# 11_FlashMemory.net
KiCad netlist of a schematic drawn in Altium Designer
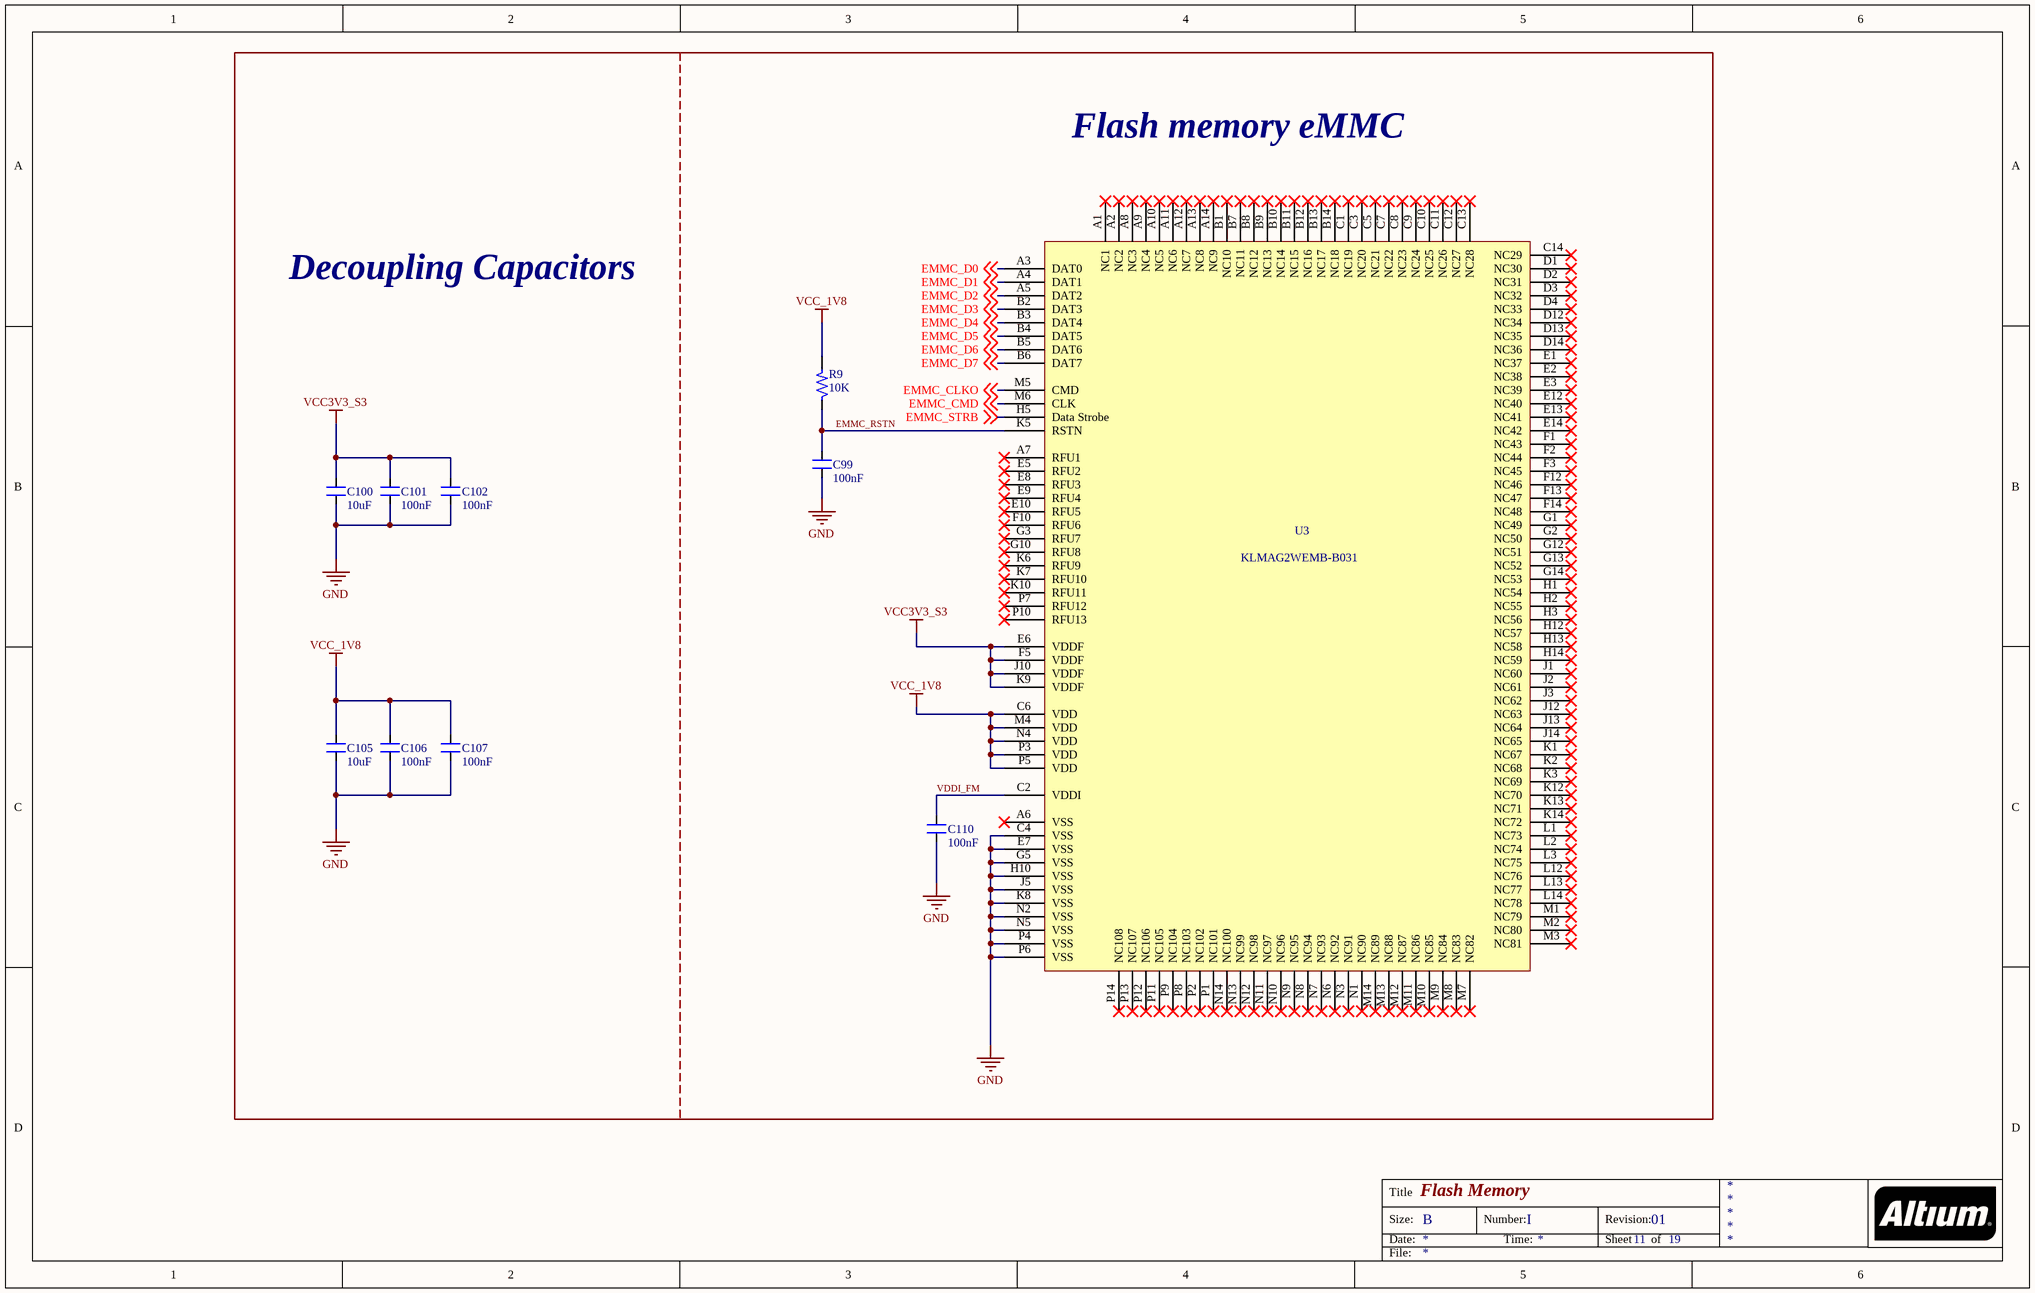
[diagram p0: [11] FlashMemory.SchDoc]

(export (version "E")
  (design (tool "Eeschema 10.0.6"))
  (components
    (comp (ref "C99")
      (value "100nF")
      (footprint "CAP_0201")
      (description "0.1µF ±10% 25V Ceramic Capacitor X5R 0201 (0603 Metric)")
      (fields
        (field (name "MANUFACTURER") "TDK Corporation")
        (field (name "MANUFACTURER PART NUMBER") "C0603X5R1E104K030BB")
      )
      (libsource (lib "EsteemPCB_SOM_Course_intlib") (part "CAP_100nF-25V-10%-0201"))
    )
    (comp (ref "C100")
      (value "10uF")
      (footprint "CAP_0603")
      (description "10µF ±10% 25V Ceramic Capacitor X5R 0603 (1608 Metric)")
      (fields
        (field (name "MANUFACTURER") "Murata Electronics")
        (field (name "MANUFACTURER PART NUMBER") "GRM188R61E106KA73D")
      )
      (libsource (lib "EsteemPCB_SOM_Course_intlib") (part "CAP_10uF-25V-10%-0603"))
    )
    (comp (ref "C101")
      (value "100nF")
      (footprint "CAP_0201")
      (description "0.1µF ±10% 25V Ceramic Capacitor X5R 0201 (0603 Metric)")
      (fields
        (field (name "MANUFACTURER") "TDK Corporation")
        (field (name "MANUFACTURER PART NUMBER") "C0603X5R1E104K030BB")
      )
      (libsource (lib "EsteemPCB_SOM_Course_intlib") (part "CAP_100nF-25V-10%-0201"))
    )
    (comp (ref "C102")
      (value "100nF")
      (footprint "CAP_0201")
      (description "0.1µF ±10% 25V Ceramic Capacitor X5R 0201 (0603 Metric)")
      (fields
        (field (name "MANUFACTURER") "TDK Corporation")
        (field (name "MANUFACTURER PART NUMBER") "C0603X5R1E104K030BB")
      )
      (libsource (lib "EsteemPCB_SOM_Course_intlib") (part "CAP_100nF-25V-10%-0201"))
    )
    (comp (ref "C105")
      (value "10uF")
      (footprint "CAP_0603")
      (description "10µF ±10% 25V Ceramic Capacitor X5R 0603 (1608 Metric)")
      (fields
        (field (name "MANUFACTURER") "Murata Electronics")
        (field (name "MANUFACTURER PART NUMBER") "GRM188R61E106KA73D")
      )
      (libsource (lib "EsteemPCB_SOM_Course_intlib") (part "CAP_10uF-25V-10%-0603"))
    )
    (comp (ref "C106")
      (value "100nF")
      (footprint "CAP_0201")
      (description "0.1µF ±10% 25V Ceramic Capacitor X5R 0201 (0603 Metric)")
      (fields
        (field (name "MANUFACTURER") "TDK Corporation")
        (field (name "MANUFACTURER PART NUMBER") "C0603X5R1E104K030BB")
      )
      (libsource (lib "EsteemPCB_SOM_Course_intlib") (part "CAP_100nF-25V-10%-0201"))
    )
    (comp (ref "C107")
      (value "100nF")
      (footprint "CAP_0201")
      (description "0.1µF ±10% 25V Ceramic Capacitor X5R 0201 (0603 Metric)")
      (fields
        (field (name "MANUFACTURER") "TDK Corporation")
        (field (name "MANUFACTURER PART NUMBER") "C0603X5R1E104K030BB")
      )
      (libsource (lib "EsteemPCB_SOM_Course_intlib") (part "CAP_100nF-25V-10%-0201"))
    )
    (comp (ref "C110")
      (value "100nF")
      (footprint "CAP_0201")
      (description "0.1µF ±10% 25V Ceramic Capacitor X5R 0201 (0603 Metric)")
      (fields
        (field (name "MANUFACTURER") "TDK Corporation")
        (field (name "MANUFACTURER PART NUMBER") "C0603X5R1E104K030BB")
      )
      (libsource (lib "EsteemPCB_SOM_Course_intlib") (part "CAP_100nF-25V-10%-0201"))
    )
    (comp (ref "R9")
      (value "10K")
      (footprint "RES_0201")
      (description "10 kOhms ±1% 0.05W, 1/20W Chip Resistor 0201 (0603 Metric) Thick Film")
      (fields
        (field (name "MANUFACTURER") "Stackpole Electronics Inc")
        (field (name "MANUFACTURER PART NUMBER") "RMCF0201FT10K0")
      )
      (libsource (lib "EsteemPCB_SOM_Course_intlib") (part "RES_10K-0.05W-1%-0201"))
    )
    (comp (ref "U3")
      (value "KLMAG2WEMB-B031")
      (footprint "BGA153C50P14X14_1150X1300X70")
      (description "16GB NAND Flash Memory")
      (fields (field (name "MANUFACTURER") "Samsung Electronics"))
      (libsource (lib "EsteemPCB_SOM_Course_intlib") (part "IC_KLMAG2WEMB-B031"))
    )
  )
  (nets
    (net (code "1") (name "/EMMC_RSTN") (class "Default")
      (node (ref "C99") (pin "2") (pinfunction "2_2") (pintype "passive"))
      (node (ref "R9") (pin "1") (pinfunction "1_1") (pintype "passive"))
      (node (ref "U3") (pin "K5") (pinfunction "RSTN_K5") (pintype "passive"))
    )
    (net (code "2") (name "/VDDI_FM") (class "Default")
      (node (ref "C110") (pin "2") (pinfunction "2_2") (pintype "passive"))
      (node (ref "U3") (pin "C2") (pinfunction "VDDI_C2") (pintype "passive"))
    )
    (net (code "3") (name "EMMC_CLKO") (class "Default")
      (node (ref "U3") (pin "M5") (pinfunction "CMD_M5") (pintype "passive"))
    )
    (net (code "4") (name "EMMC_CMD") (class "Default")
      (node (ref "U3") (pin "M6") (pinfunction "CLK_M6") (pintype "passive"))
    )
    (net (code "5") (name "EMMC_D0") (class "Default")
      (node (ref "U3") (pin "A3") (pinfunction "DAT0_A3") (pintype "passive"))
    )
    (net (code "6") (name "EMMC_D1") (class "Default")
      (node (ref "U3") (pin "A4") (pinfunction "DAT1_A4") (pintype "passive"))
    )
    (net (code "7") (name "EMMC_D2") (class "Default")
      (node (ref "U3") (pin "A5") (pinfunction "DAT2_A5") (pintype "passive"))
    )
    (net (code "8") (name "EMMC_D3") (class "Default")
      (node (ref "U3") (pin "B2") (pinfunction "DAT3_B2") (pintype "passive"))
    )
    (net (code "9") (name "EMMC_D4") (class "Default")
      (node (ref "U3") (pin "B3") (pinfunction "DAT4_B3") (pintype "passive"))
    )
    (net (code "10") (name "EMMC_D5") (class "Default")
      (node (ref "U3") (pin "B4") (pinfunction "DAT5_B4") (pintype "passive"))
    )
    (net (code "11") (name "EMMC_D6") (class "Default")
      (node (ref "U3") (pin "B5") (pinfunction "DAT6_B5") (pintype "passive"))
    )
    (net (code "12") (name "EMMC_D7") (class "Default")
      (node (ref "U3") (pin "B6") (pinfunction "DAT7_B6") (pintype "passive"))
    )
    (net (code "13") (name "EMMC_STRB") (class "Default")
      (node (ref "U3") (pin "H5") (pinfunction "Data_Strobe_H5") (pintype "passive"))
    )
    (net (code "14") (name "GND") (class "Default")
      (node (ref "C100") (pin "1") (pinfunction "1_1") (pintype "passive"))
      (node (ref "C101") (pin "1") (pinfunction "1_1") (pintype "passive"))
      (node (ref "C102") (pin "1") (pinfunction "1_1") (pintype "passive"))
      (node (ref "C105") (pin "1") (pinfunction "1_1") (pintype "passive"))
      (node (ref "C106") (pin "1") (pinfunction "1_1") (pintype "passive"))
      (node (ref "C107") (pin "1") (pinfunction "1_1") (pintype "passive"))
      (node (ref "C110") (pin "1") (pinfunction "1_1") (pintype "passive"))
      (node (ref "C99") (pin "1") (pinfunction "1_1") (pintype "passive"))
      (node (ref "U3") (pin "C4") (pinfunction "VSS_C4") (pintype "passive"))
      (node (ref "U3") (pin "E7") (pinfunction "VSS_E7") (pintype "passive"))
      (node (ref "U3") (pin "G5") (pinfunction "VSS_G5") (pintype "passive"))
      (node (ref "U3") (pin "H10") (pinfunction "VSS_H10") (pintype "passive"))
      (node (ref "U3") (pin "J5") (pinfunction "VSS_J5") (pintype "passive"))
      (node (ref "U3") (pin "K8") (pinfunction "VSS_K8") (pintype "passive"))
      (node (ref "U3") (pin "N2") (pinfunction "VSS_N2") (pintype "passive"))
      (node (ref "U3") (pin "N5") (pinfunction "VSS_N5") (pintype "passive"))
      (node (ref "U3") (pin "P4") (pinfunction "VSS_P4") (pintype "passive"))
      (node (ref "U3") (pin "P6") (pinfunction "VSS_P6") (pintype "passive"))
    )
    (net (code "15") (name "VCC3V3_S3") (class "Default")
      (node (ref "C100") (pin "2") (pinfunction "2_2") (pintype "passive"))
      (node (ref "C101") (pin "2") (pinfunction "2_2") (pintype "passive"))
      (node (ref "C102") (pin "2") (pinfunction "2_2") (pintype "passive"))
      (node (ref "U3") (pin "E6") (pinfunction "VDDF_E6") (pintype "passive"))
      (node (ref "U3") (pin "F5") (pinfunction "VDDF_F5") (pintype "passive"))
      (node (ref "U3") (pin "J10") (pinfunction "VDDF_J10") (pintype "passive"))
      (node (ref "U3") (pin "K9") (pinfunction "VDDF_K9") (pintype "passive"))
    )
    (net (code "16") (name "VCC_1V8") (class "Default")
      (node (ref "C105") (pin "2") (pinfunction "2_2") (pintype "passive"))
      (node (ref "C106") (pin "2") (pinfunction "2_2") (pintype "passive"))
      (node (ref "C107") (pin "2") (pinfunction "2_2") (pintype "passive"))
      (node (ref "R9") (pin "2") (pinfunction "2_2") (pintype "passive"))
      (node (ref "U3") (pin "C6") (pinfunction "VDD_C6") (pintype "passive"))
      (node (ref "U3") (pin "M4") (pinfunction "VDD_M4") (pintype "passive"))
      (node (ref "U3") (pin "N4") (pinfunction "VDD_N4") (pintype "passive"))
      (node (ref "U3") (pin "P3") (pinfunction "VDD_P3") (pintype "passive"))
      (node (ref "U3") (pin "P5") (pinfunction "VDD_P5") (pintype "passive"))
    )
    (net (code "17") (name "unconnected-(U3-NC1-PadA1)") (class "Default")
      (node (ref "U3") (pin "A1") (pinfunction "NC1_A1") (pintype "passive+no_connect"))
    )
    (net (code "18") (name "unconnected-(U3-NC2-PadA2)") (class "Default")
      (node (ref "U3") (pin "A2") (pinfunction "NC2_A2") (pintype "passive+no_connect"))
    )
    (net (code "19") (name "unconnected-(U3-NC3-PadA8)") (class "Default")
      (node (ref "U3") (pin "A8") (pinfunction "NC3_A8") (pintype "passive+no_connect"))
    )
    (net (code "20") (name "unconnected-(U3-NC4-PadA9)") (class "Default")
      (node (ref "U3") (pin "A9") (pinfunction "NC4_A9") (pintype "passive+no_connect"))
    )
    (net (code "21") (name "unconnected-(U3-NC5-PadA10)") (class "Default")
      (node (ref "U3") (pin "A10") (pinfunction "NC5_A10") (pintype "passive+no_connect"))
    )
    (net (code "22") (name "unconnected-(U3-NC6-PadA11)") (class "Default")
      (node (ref "U3") (pin "A11") (pinfunction "NC6_A11") (pintype "passive+no_connect"))
    )
    (net (code "23") (name "unconnected-(U3-NC7-PadA12)") (class "Default")
      (node (ref "U3") (pin "A12") (pinfunction "NC7_A12") (pintype "passive+no_connect"))
    )
    (net (code "24") (name "unconnected-(U3-NC8-PadA13)") (class "Default")
      (node (ref "U3") (pin "A13") (pinfunction "NC8_A13") (pintype "passive+no_connect"))
    )
    (net (code "25") (name "unconnected-(U3-NC9-PadA14)") (class "Default")
      (node (ref "U3") (pin "A14") (pinfunction "NC9_A14") (pintype "passive+no_connect"))
    )
    (net (code "26") (name "unconnected-(U3-NC10-PadB1)") (class "Default")
      (node (ref "U3") (pin "B1") (pinfunction "NC10_B1") (pintype "passive+no_connect"))
    )
    (net (code "27") (name "unconnected-(U3-NC11-PadB7)") (class "Default")
      (node (ref "U3") (pin "B7") (pinfunction "NC11_B7") (pintype "passive+no_connect"))
    )
    (net (code "28") (name "unconnected-(U3-NC12-PadB8)") (class "Default")
      (node (ref "U3") (pin "B8") (pinfunction "NC12_B8") (pintype "passive+no_connect"))
    )
    (net (code "29") (name "unconnected-(U3-NC13-PadB9)") (class "Default")
      (node (ref "U3") (pin "B9") (pinfunction "NC13_B9") (pintype "passive+no_connect"))
    )
    (net (code "30") (name "unconnected-(U3-NC14-PadB10)") (class "Default")
      (node (ref "U3") (pin "B10") (pinfunction "NC14_B10") (pintype "passive+no_connect"))
    )
    (net (code "31") (name "unconnected-(U3-NC15-PadB11)") (class "Default")
      (node (ref "U3") (pin "B11") (pinfunction "NC15_B11") (pintype "passive+no_connect"))
    )
    (net (code "32") (name "unconnected-(U3-NC16-PadB12)") (class "Default")
      (node (ref "U3") (pin "B12") (pinfunction "NC16_B12") (pintype "passive+no_connect"))
    )
    (net (code "33") (name "unconnected-(U3-NC17-PadB13)") (class "Default")
      (node (ref "U3") (pin "B13") (pinfunction "NC17_B13") (pintype "passive+no_connect"))
    )
    (net (code "34") (name "unconnected-(U3-NC18-PadB14)") (class "Default")
      (node (ref "U3") (pin "B14") (pinfunction "NC18_B14") (pintype "passive+no_connect"))
    )
    (net (code "35") (name "unconnected-(U3-NC19-PadC1)") (class "Default")
      (node (ref "U3") (pin "C1") (pinfunction "NC19_C1") (pintype "passive+no_connect"))
    )
    (net (code "36") (name "unconnected-(U3-NC20-PadC3)") (class "Default")
      (node (ref "U3") (pin "C3") (pinfunction "NC20_C3") (pintype "passive+no_connect"))
    )
    (net (code "37") (name "unconnected-(U3-NC21-PadC5)") (class "Default")
      (node (ref "U3") (pin "C5") (pinfunction "NC21_C5") (pintype "passive+no_connect"))
    )
    (net (code "38") (name "unconnected-(U3-NC22-PadC7)") (class "Default")
      (node (ref "U3") (pin "C7") (pinfunction "NC22_C7") (pintype "passive+no_connect"))
    )
    (net (code "39") (name "unconnected-(U3-NC23-PadC8)") (class "Default")
      (node (ref "U3") (pin "C8") (pinfunction "NC23_C8") (pintype "passive+no_connect"))
    )
    (net (code "40") (name "unconnected-(U3-NC24-PadC9)") (class "Default")
      (node (ref "U3") (pin "C9") (pinfunction "NC24_C9") (pintype "passive+no_connect"))
    )
    (net (code "41") (name "unconnected-(U3-NC25-PadC10)") (class "Default")
      (node (ref "U3") (pin "C10") (pinfunction "NC25_C10") (pintype "passive+no_connect"))
    )
    (net (code "42") (name "unconnected-(U3-NC26-PadC11)") (class "Default")
      (node (ref "U3") (pin "C11") (pinfunction "NC26_C11") (pintype "passive+no_connect"))
    )
    (net (code "43") (name "unconnected-(U3-NC27-PadC12)") (class "Default")
      (node (ref "U3") (pin "C12") (pinfunction "NC27_C12") (pintype "passive+no_connect"))
    )
    (net (code "44") (name "unconnected-(U3-NC28-PadC13)") (class "Default")
      (node (ref "U3") (pin "C13") (pinfunction "NC28_C13") (pintype "passive+no_connect"))
    )
    (net (code "45") (name "unconnected-(U3-NC29-PadC14)") (class "Default")
      (node (ref "U3") (pin "C14") (pinfunction "NC29_C14") (pintype "passive+no_connect"))
    )
    (net (code "46") (name "unconnected-(U3-NC30-PadD1)") (class "Default")
      (node (ref "U3") (pin "D1") (pinfunction "NC30_D1") (pintype "passive+no_connect"))
    )
    (net (code "47") (name "unconnected-(U3-NC31-PadD2)") (class "Default")
      (node (ref "U3") (pin "D2") (pinfunction "NC31_D2") (pintype "passive+no_connect"))
    )
    (net (code "48") (name "unconnected-(U3-NC32-PadD3)") (class "Default")
      (node (ref "U3") (pin "D3") (pinfunction "NC32_D3") (pintype "passive+no_connect"))
    )
    (net (code "49") (name "unconnected-(U3-NC33-PadD4)") (class "Default")
      (node (ref "U3") (pin "D4") (pinfunction "NC33_D4") (pintype "passive+no_connect"))
    )
    (net (code "50") (name "unconnected-(U3-NC34-PadD12)") (class "Default")
      (node (ref "U3") (pin "D12") (pinfunction "NC34_D12") (pintype "passive+no_connect"))
    )
    (net (code "51") (name "unconnected-(U3-NC35-PadD13)") (class "Default")
      (node (ref "U3") (pin "D13") (pinfunction "NC35_D13") (pintype "passive+no_connect"))
    )
    (net (code "52") (name "unconnected-(U3-NC36-PadD14)") (class "Default")
      (node (ref "U3") (pin "D14") (pinfunction "NC36_D14") (pintype "passive+no_connect"))
    )
    (net (code "53") (name "unconnected-(U3-NC37-PadE1)") (class "Default")
      (node (ref "U3") (pin "E1") (pinfunction "NC37_E1") (pintype "passive+no_connect"))
    )
    (net (code "54") (name "unconnected-(U3-NC38-PadE2)") (class "Default")
      (node (ref "U3") (pin "E2") (pinfunction "NC38_E2") (pintype "passive+no_connect"))
    )
    (net (code "55") (name "unconnected-(U3-NC39-PadE3)") (class "Default")
      (node (ref "U3") (pin "E3") (pinfunction "NC39_E3") (pintype "passive+no_connect"))
    )
    (net (code "56") (name "unconnected-(U3-NC40-PadE12)") (class "Default")
      (node (ref "U3") (pin "E12") (pinfunction "NC40_E12") (pintype "passive+no_connect"))
    )
    (net (code "57") (name "unconnected-(U3-NC41-PadE13)") (class "Default")
      (node (ref "U3") (pin "E13") (pinfunction "NC41_E13") (pintype "passive+no_connect"))
    )
    (net (code "58") (name "unconnected-(U3-NC42-PadE14)") (class "Default")
      (node (ref "U3") (pin "E14") (pinfunction "NC42_E14") (pintype "passive+no_connect"))
    )
    (net (code "59") (name "unconnected-(U3-NC43-PadF1)") (class "Default")
      (node (ref "U3") (pin "F1") (pinfunction "NC43_F1") (pintype "passive+no_connect"))
    )
    (net (code "60") (name "unconnected-(U3-NC44-PadF2)") (class "Default")
      (node (ref "U3") (pin "F2") (pinfunction "NC44_F2") (pintype "passive+no_connect"))
    )
    (net (code "61") (name "unconnected-(U3-NC45-PadF3)") (class "Default")
      (node (ref "U3") (pin "F3") (pinfunction "NC45_F3") (pintype "passive+no_connect"))
    )
    (net (code "62") (name "unconnected-(U3-NC46-PadF12)") (class "Default")
      (node (ref "U3") (pin "F12") (pinfunction "NC46_F12") (pintype "passive+no_connect"))
    )
    (net (code "63") (name "unconnected-(U3-NC47-PadF13)") (class "Default")
      (node (ref "U3") (pin "F13") (pinfunction "NC47_F13") (pintype "passive+no_connect"))
    )
    (net (code "64") (name "unconnected-(U3-NC48-PadF14)") (class "Default")
      (node (ref "U3") (pin "F14") (pinfunction "NC48_F14") (pintype "passive+no_connect"))
    )
    (net (code "65") (name "unconnected-(U3-NC49-PadG1)") (class "Default")
      (node (ref "U3") (pin "G1") (pinfunction "NC49_G1") (pintype "passive+no_connect"))
    )
    (net (code "66") (name "unconnected-(U3-NC50-PadG2)") (class "Default")
      (node (ref "U3") (pin "G2") (pinfunction "NC50_G2") (pintype "passive+no_connect"))
    )
    (net (code "67") (name "unconnected-(U3-NC51-PadG12)") (class "Default")
      (node (ref "U3") (pin "G12") (pinfunction "NC51_G12") (pintype "passive+no_connect"))
    )
    (net (code "68") (name "unconnected-(U3-NC52-PadG13)") (class "Default")
      (node (ref "U3") (pin "G13") (pinfunction "NC52_G13") (pintype "passive+no_connect"))
    )
    (net (code "69") (name "unconnected-(U3-NC53-PadG14)") (class "Default")
      (node (ref "U3") (pin "G14") (pinfunction "NC53_G14") (pintype "passive+no_connect"))
    )
    (net (code "70") (name "unconnected-(U3-NC54-PadH1)") (class "Default")
      (node (ref "U3") (pin "H1") (pinfunction "NC54_H1") (pintype "passive+no_connect"))
    )
    (net (code "71") (name "unconnected-(U3-NC55-PadH2)") (class "Default")
      (node (ref "U3") (pin "H2") (pinfunction "NC55_H2") (pintype "passive+no_connect"))
    )
    (net (code "72") (name "unconnected-(U3-NC56-PadH3)") (class "Default")
      (node (ref "U3") (pin "H3") (pinfunction "NC56_H3") (pintype "passive+no_connect"))
    )
    (net (code "73") (name "unconnected-(U3-NC57-PadH12)") (class "Default")
      (node (ref "U3") (pin "H12") (pinfunction "NC57_H12") (pintype "passive+no_connect"))
    )
    (net (code "74") (name "unconnected-(U3-NC58-PadH13)") (class "Default")
      (node (ref "U3") (pin "H13") (pinfunction "NC58_H13") (pintype "passive+no_connect"))
    )
    (net (code "75") (name "unconnected-(U3-NC59-PadH14)") (class "Default")
      (node (ref "U3") (pin "H14") (pinfunction "NC59_H14") (pintype "passive+no_connect"))
    )
    (net (code "76") (name "unconnected-(U3-NC60-PadJ1)") (class "Default")
      (node (ref "U3") (pin "J1") (pinfunction "NC60_J1") (pintype "passive+no_connect"))
    )
    (net (code "77") (name "unconnected-(U3-NC61-PadJ2)") (class "Default")
      (node (ref "U3") (pin "J2") (pinfunction "NC61_J2") (pintype "passive+no_connect"))
    )
    (net (code "78") (name "unconnected-(U3-NC62-PadJ3)") (class "Default")
      (node (ref "U3") (pin "J3") (pinfunction "NC62_J3") (pintype "passive+no_connect"))
    )
    (net (code "79") (name "unconnected-(U3-NC63-PadJ12)") (class "Default")
      (node (ref "U3") (pin "J12") (pinfunction "NC63_J12") (pintype "passive+no_connect"))
    )
    (net (code "80") (name "unconnected-(U3-NC64-PadJ13)") (class "Default")
      (node (ref "U3") (pin "J13") (pinfunction "NC64_J13") (pintype "passive+no_connect"))
    )
    (net (code "81") (name "unconnected-(U3-NC65-PadJ14)") (class "Default")
      (node (ref "U3") (pin "J14") (pinfunction "NC65_J14") (pintype "passive+no_connect"))
    )
    (net (code "82") (name "unconnected-(U3-NC67-PadK1)") (class "Default")
      (node (ref "U3") (pin "K1") (pinfunction "NC67_K1") (pintype "passive+no_connect"))
    )
    (net (code "83") (name "unconnected-(U3-NC68-PadK2)") (class "Default")
      (node (ref "U3") (pin "K2") (pinfunction "NC68_K2") (pintype "passive+no_connect"))
    )
    (net (code "84") (name "unconnected-(U3-NC69-PadK3)") (class "Default")
      (node (ref "U3") (pin "K3") (pinfunction "NC69_K3") (pintype "passive+no_connect"))
    )
    (net (code "85") (name "unconnected-(U3-NC70-PadK12)") (class "Default")
      (node (ref "U3") (pin "K12") (pinfunction "NC70_K12") (pintype "passive+no_connect"))
    )
    (net (code "86") (name "unconnected-(U3-NC71-PadK13)") (class "Default")
      (node (ref "U3") (pin "K13") (pinfunction "NC71_K13") (pintype "passive+no_connect"))
    )
    (net (code "87") (name "unconnected-(U3-NC72-PadK14)") (class "Default")
      (node (ref "U3") (pin "K14") (pinfunction "NC72_K14") (pintype "passive+no_connect"))
    )
    (net (code "88") (name "unconnected-(U3-NC73-PadL1)") (class "Default")
      (node (ref "U3") (pin "L1") (pinfunction "NC73_L1") (pintype "passive+no_connect"))
    )
    (net (code "89") (name "unconnected-(U3-NC74-PadL2)") (class "Default")
      (node (ref "U3") (pin "L2") (pinfunction "NC74_L2") (pintype "passive+no_connect"))
    )
    (net (code "90") (name "unconnected-(U3-NC75-PadL3)") (class "Default")
      (node (ref "U3") (pin "L3") (pinfunction "NC75_L3") (pintype "passive+no_connect"))
    )
    (net (code "91") (name "unconnected-(U3-NC76-PadL12)") (class "Default")
      (node (ref "U3") (pin "L12") (pinfunction "NC76_L12") (pintype "passive+no_connect"))
    )
    (net (code "92") (name "unconnected-(U3-NC77-PadL13)") (class "Default")
      (node (ref "U3") (pin "L13") (pinfunction "NC77_L13") (pintype "passive+no_connect"))
    )
    (net (code "93") (name "unconnected-(U3-NC78-PadL14)") (class "Default")
      (node (ref "U3") (pin "L14") (pinfunction "NC78_L14") (pintype "passive+no_connect"))
    )
    (net (code "94") (name "unconnected-(U3-NC79-PadM1)") (class "Default")
      (node (ref "U3") (pin "M1") (pinfunction "NC79_M1") (pintype "passive+no_connect"))
    )
    (net (code "95") (name "unconnected-(U3-NC80-PadM2)") (class "Default")
      (node (ref "U3") (pin "M2") (pinfunction "NC80_M2") (pintype "passive+no_connect"))
    )
    (net (code "96") (name "unconnected-(U3-NC81-PadM3)") (class "Default")
      (node (ref "U3") (pin "M3") (pinfunction "NC81_M3") (pintype "passive+no_connect"))
    )
    (net (code "97") (name "unconnected-(U3-NC82-PadM7)") (class "Default")
      (node (ref "U3") (pin "M7") (pinfunction "NC82_M7") (pintype "passive+no_connect"))
    )
    (net (code "98") (name "unconnected-(U3-NC83-PadM8)") (class "Default")
      (node (ref "U3") (pin "M8") (pinfunction "NC83_M8") (pintype "passive+no_connect"))
    )
    (net (code "99") (name "unconnected-(U3-NC84-PadM9)") (class "Default")
      (node (ref "U3") (pin "M9") (pinfunction "NC84_M9") (pintype "passive+no_connect"))
    )
    (net (code "100") (name "unconnected-(U3-NC85-PadM10)") (class "Default")
      (node (ref "U3") (pin "M10") (pinfunction "NC85_M10") (pintype "passive+no_connect"))
    )
    (net (code "101") (name "unconnected-(U3-NC86-PadM11)") (class "Default")
      (node (ref "U3") (pin "M11") (pinfunction "NC86_M11") (pintype "passive+no_connect"))
    )
    (net (code "102") (name "unconnected-(U3-NC87-PadM12)") (class "Default")
      (node (ref "U3") (pin "M12") (pinfunction "NC87_M12") (pintype "passive+no_connect"))
    )
    (net (code "103") (name "unconnected-(U3-NC88-PadM13)") (class "Default")
      (node (ref "U3") (pin "M13") (pinfunction "NC88_M13") (pintype "passive+no_connect"))
    )
    (net (code "104") (name "unconnected-(U3-NC89-PadM14)") (class "Default")
      (node (ref "U3") (pin "M14") (pinfunction "NC89_M14") (pintype "passive+no_connect"))
    )
    (net (code "105") (name "unconnected-(U3-NC90-PadN1)") (class "Default")
      (node (ref "U3") (pin "N1") (pinfunction "NC90_N1") (pintype "passive+no_connect"))
    )
    (net (code "106") (name "unconnected-(U3-NC91-PadN3)") (class "Default")
      (node (ref "U3") (pin "N3") (pinfunction "NC91_N3") (pintype "passive+no_connect"))
    )
    (net (code "107") (name "unconnected-(U3-NC92-PadN6)") (class "Default")
      (node (ref "U3") (pin "N6") (pinfunction "NC92_N6") (pintype "passive+no_connect"))
    )
    (net (code "108") (name "unconnected-(U3-NC93-PadN7)") (class "Default")
      (node (ref "U3") (pin "N7") (pinfunction "NC93_N7") (pintype "passive+no_connect"))
    )
    (net (code "109") (name "unconnected-(U3-NC94-PadN8)") (class "Default")
      (node (ref "U3") (pin "N8") (pinfunction "NC94_N8") (pintype "passive+no_connect"))
    )
    (net (code "110") (name "unconnected-(U3-NC95-PadN9)") (class "Default")
      (node (ref "U3") (pin "N9") (pinfunction "NC95_N9") (pintype "passive+no_connect"))
    )
    (net (code "111") (name "unconnected-(U3-NC96-PadN10)") (class "Default")
      (node (ref "U3") (pin "N10") (pinfunction "NC96_N10") (pintype "passive+no_connect"))
    )
    (net (code "112") (name "unconnected-(U3-NC97-PadN11)") (class "Default")
      (node (ref "U3") (pin "N11") (pinfunction "NC97_N11") (pintype "passive+no_connect"))
    )
    (net (code "113") (name "unconnected-(U3-NC98-PadN12)") (class "Default")
      (node (ref "U3") (pin "N12") (pinfunction "NC98_N12") (pintype "passive+no_connect"))
    )
    (net (code "114") (name "unconnected-(U3-NC99-PadN13)") (class "Default")
      (node (ref "U3") (pin "N13") (pinfunction "NC99_N13") (pintype "passive+no_connect"))
    )
    (net (code "115") (name "unconnected-(U3-NC100-PadN14)") (class "Default")
      (node (ref "U3") (pin "N14") (pinfunction "NC100_N14") (pintype "passive+no_connect"))
    )
    (net (code "116") (name "unconnected-(U3-NC101-PadP1)") (class "Default")
      (node (ref "U3") (pin "P1") (pinfunction "NC101_P1") (pintype "passive+no_connect"))
    )
    (net (code "117") (name "unconnected-(U3-NC102-PadP2)") (class "Default")
      (node (ref "U3") (pin "P2") (pinfunction "NC102_P2") (pintype "passive+no_connect"))
    )
    (net (code "118") (name "unconnected-(U3-NC103-PadP8)") (class "Default")
      (node (ref "U3") (pin "P8") (pinfunction "NC103_P8") (pintype "passive+no_connect"))
    )
    (net (code "119") (name "unconnected-(U3-NC104-PadP9)") (class "Default")
      (node (ref "U3") (pin "P9") (pinfunction "NC104_P9") (pintype "passive+no_connect"))
    )
    (net (code "120") (name "unconnected-(U3-NC105-PadP11)") (class "Default")
      (node (ref "U3") (pin "P11") (pinfunction "NC105_P11") (pintype "passive+no_connect"))
    )
    (net (code "121") (name "unconnected-(U3-NC106-PadP12)") (class "Default")
      (node (ref "U3") (pin "P12") (pinfunction "NC106_P12") (pintype "passive+no_connect"))
    )
    (net (code "122") (name "unconnected-(U3-NC107-PadP13)") (class "Default")
      (node (ref "U3") (pin "P13") (pinfunction "NC107_P13") (pintype "passive+no_connect"))
    )
    (net (code "123") (name "unconnected-(U3-NC108-PadP14)") (class "Default")
      (node (ref "U3") (pin "P14") (pinfunction "NC108_P14") (pintype "passive+no_connect"))
    )
    (net (code "124") (name "unconnected-(U3-RFU1-PadA7)") (class "Default")
      (node (ref "U3") (pin "A7") (pinfunction "RFU1_A7") (pintype "passive+no_connect"))
    )
    (net (code "125") (name "unconnected-(U3-RFU2-PadE5)") (class "Default")
      (node (ref "U3") (pin "E5") (pinfunction "RFU2_E5") (pintype "passive+no_connect"))
    )
    (net (code "126") (name "unconnected-(U3-RFU3-PadE8)") (class "Default")
      (node (ref "U3") (pin "E8") (pinfunction "RFU3_E8") (pintype "passive+no_connect"))
    )
    (net (code "127") (name "unconnected-(U3-RFU4-PadE9)") (class "Default")
      (node (ref "U3") (pin "E9") (pinfunction "RFU4_E9") (pintype "passive+no_connect"))
    )
    (net (code "128") (name "unconnected-(U3-RFU5-PadE10)") (class "Default")
      (node (ref "U3") (pin "E10") (pinfunction "RFU5_E10") (pintype "passive+no_connect"))
    )
    (net (code "129") (name "unconnected-(U3-RFU6-PadF10)") (class "Default")
      (node (ref "U3") (pin "F10") (pinfunction "RFU6_F10") (pintype "passive+no_connect"))
    )
    (net (code "130") (name "unconnected-(U3-RFU7-PadG3)") (class "Default")
      (node (ref "U3") (pin "G3") (pinfunction "RFU7_G3") (pintype "passive+no_connect"))
    )
    (net (code "131") (name "unconnected-(U3-RFU8-PadG10)") (class "Default")
      (node (ref "U3") (pin "G10") (pinfunction "RFU8_G10") (pintype "passive+no_connect"))
    )
    (net (code "132") (name "unconnected-(U3-RFU9-PadK6)") (class "Default")
      (node (ref "U3") (pin "K6") (pinfunction "RFU9_K6") (pintype "passive+no_connect"))
    )
    (net (code "133") (name "unconnected-(U3-RFU10-PadK7)") (class "Default")
      (node (ref "U3") (pin "K7") (pinfunction "RFU10_K7") (pintype "passive+no_connect"))
    )
    (net (code "134") (name "unconnected-(U3-RFU11-PadK10)") (class "Default")
      (node (ref "U3") (pin "K10") (pinfunction "RFU11_K10") (pintype "passive+no_connect"))
    )
    (net (code "135") (name "unconnected-(U3-RFU12-PadP7)") (class "Default")
      (node (ref "U3") (pin "P7") (pinfunction "RFU12_P7") (pintype "passive+no_connect"))
    )
    (net (code "136") (name "unconnected-(U3-RFU13-PadP10)") (class "Default")
      (node (ref "U3") (pin "P10") (pinfunction "RFU13_P10") (pintype "passive+no_connect"))
    )
    (net (code "137") (name "unconnected-(U3-VSS-PadA6)") (class "Default")
      (node (ref "U3") (pin "A6") (pinfunction "VSS_A6") (pintype "passive+no_connect"))
    )
  )
)
